# greento_schematic.net
KiCad netlist of a schematic drawn in Altium Designer
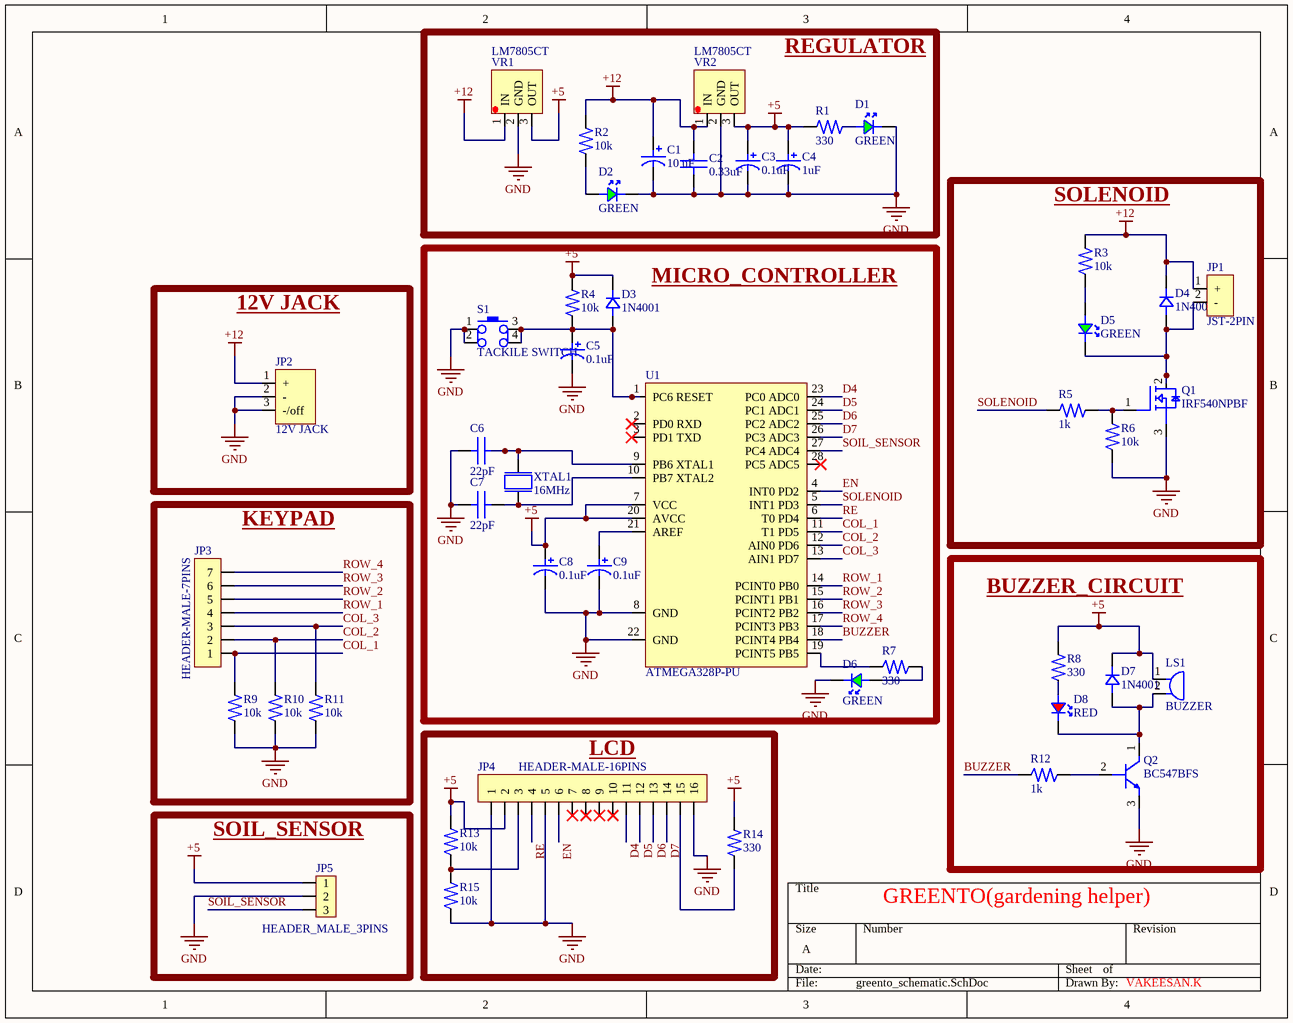
[diagram p0: greento_schematic.SchDoc]

(export (version "E")
  (design (tool "Eeschema 10.0.6"))
  (components
    (comp (ref "C1")
      (value "CAP ALUM 10UF 20% 450V RADIAL")
      (footprint "CAP ALUM 10UF 20% 450V RADIAL")
      (description "BXC Series 450 V 10 µF 10x20mm Aluminum Electrolytic Capacitor")
      (fields
        (field (name "MANUFACTURER") "Rubycon")
        (field (name "MANUFACTURER PART NUMBER") "450BXC10MEFC10X20")
        (field (name "SUPPLIER PART NUMBER 1") "10 uF")
      )
      (libsource (lib "schlib2") (part "450BXC10MEFC10X20"))
    )
    (comp (ref "C2")
      (value "CAP CER 0.33UF 50V X7R RADIAL")
      (footprint "CAP CER 0.33UF 50V X7R RADIAL")
      (description "Cap Ceramic 0.33uF 50V X7R 10% Radial 5mm 125C Bulk")
      (fields
        (field (name "MANUFACTURER") "TDK")
        (field (name "MANUFACTURER PART NUMBER") "FK24X7R1H334K")
        (field (name "SUPPLIER PART NUMBER 1") "0.33uF")
      )
      (libsource (lib "schlib2") (part "FK24X7R1H334K"))
    )
    (comp (ref "C3")
      (value "CAP ALUM 0.1UF 20% 50V RADIAL")
      (footprint "CAP ALUM 0.1UF 20% 50V RADIAL")
      (fields
        (field (name "MANUFACTURER") "Nichicon")
        (field (name "MANUFACTURER PART NUMBER") "UVZ1H0R1MDD1TD")
        (field (name "TOLERANCE") "20%")
        (field (name "SUPPLIER PART NUMBER 1") "0.1uF")
      )
      (libsource (lib "schlib2") (part "UVZ1H0R1MDD1TD"))
    )
    (comp (ref "C4")
      (value "CAP ALUM 1UF 20% 100V RADIAL")
      (footprint "CAP ALUM 1UF 20% 100V RADIAL")
      (description "Cap Aluminum 1uF 100V 20% (5 X 11mm) Radial 2.5mm 21mA 2000 hr 85°C Ammo Pack")
      (fields
        (field (name "MANUFACTURER") "Nichicon")
        (field (name "MANUFACTURER PART NUMBER") "UVR2A010MDD1TD")
        (field (name "SUPPLIER PART NUMBER 1") "1uF")
      )
      (libsource (lib "schlib2") (part "UVR2A010MDD1TD"))
    )
    (comp (ref "C5")
      (value "CAP ALUM 0.1UF 20% 50V RADIAL")
      (footprint "CAP ALUM 0.1UF 20% 50V RADIAL")
      (fields
        (field (name "MANUFACTURER") "Nichicon")
        (field (name "MANUFACTURER PART NUMBER") "UVZ1H0R1MDD1TD")
        (field (name "TOLERANCE") "20%")
        (field (name "SUPPLIER PART NUMBER 1") "0.1uF")
      )
      (libsource (lib "schlib2") (part "UVZ1H0R1MDD1TD"))
    )
    (comp (ref "C6")
      (value "CAP CER 22PF 200V NP0 RADIAL")
      (footprint "CAP CER 22PF 200V NP0 RADIAL")
      (description "Cap Ceramic 22pF 200V C0G 5% Radial 5.08mm 125°C Extreme Low ESR Bulk")
      (fields
        (field (name "MANUFACTURER") "KEMET")
        (field (name "MANUFACTURER PART NUMBER") "C317C220J2G5TA")
        (field (name "SUPPLIER PART NUMBER 1") "22pF")
      )
      (libsource (lib "schlib2") (part "C317C220J2G5TA"))
    )
    (comp (ref "C7")
      (value "CAP CER 22PF 200V NP0 RADIAL")
      (footprint "CAP CER 22PF 200V NP0 RADIAL")
      (description "Cap Ceramic 22pF 200V C0G 5% Radial 5.08mm 125°C Extreme Low ESR Bulk")
      (fields
        (field (name "MANUFACTURER") "KEMET")
        (field (name "MANUFACTURER PART NUMBER") "C317C220J2G5TA")
        (field (name "SUPPLIER PART NUMBER 1") "22pF")
      )
      (libsource (lib "schlib2") (part "C317C220J2G5TA"))
    )
    (comp (ref "C8")
      (value "CAP ALUM 0.1UF 20% 50V RADIAL")
      (footprint "CAP ALUM 0.1UF 20% 50V RADIAL")
      (fields
        (field (name "MANUFACTURER") "Nichicon")
        (field (name "MANUFACTURER PART NUMBER") "UVZ1H0R1MDD1TD")
        (field (name "TOLERANCE") "20%")
        (field (name "SUPPLIER PART NUMBER 1") "0.1uF")
      )
      (libsource (lib "schlib2") (part "UVZ1H0R1MDD1TD"))
    )
    (comp (ref "C9")
      (value "CAP ALUM 0.1UF 20% 50V RADIAL")
      (footprint "CAP ALUM 0.1UF 20% 50V RADIAL")
      (fields
        (field (name "MANUFACTURER") "Nichicon")
        (field (name "MANUFACTURER PART NUMBER") "UVZ1H0R1MDD1TD")
        (field (name "TOLERANCE") "20%")
        (field (name "SUPPLIER PART NUMBER 1") "0.1uF")
      )
      (libsource (lib "schlib2") (part "UVZ1H0R1MDD1TD"))
    )
    (comp (ref "D1")
      (value "LED GREEN CLEAR T-1 3/4 T/H")
      (footprint "LED GREEN CLEAR T-1 3/4 T/H")
      (description "Green 5 mm T-13/4 40° Diffused 29 mcd 2.1 V LED Through Hole")
      (fields
        (field (name "MANUFACTURER") "Vishay Lite-On")
        (field (name "MANUFACTURER PART NUMBER") "LTL-307GE")
        (field (name "SUPPLIER PART NUMBER 1") "GREEN")
      )
      (libsource (lib "schlib2") (part "LTL-307GE"))
    )
    (comp (ref "D2")
      (value "LED GREEN CLEAR T-1 3/4 T/H")
      (footprint "LED GREEN CLEAR T-1 3/4 T/H")
      (description "Green 5 mm T-13/4 40° Diffused 29 mcd 2.1 V LED Through Hole")
      (fields
        (field (name "MANUFACTURER") "Vishay Lite-On")
        (field (name "MANUFACTURER PART NUMBER") "LTL-307GE")
        (field (name "SUPPLIER PART NUMBER 1") "GREEN")
      )
      (libsource (lib "schlib2") (part "LTL-307GE"))
    )
    (comp (ref "D3")
      (value "DIODE GEN PURP 50V 1A DO41")
      (footprint "Diode 1N001")
      (description "Diode Switching 50V 1A 2-Pin DO-41 Bag")
      (fields
        (field (name "MANUFACTURER") "ON Semiconductor")
        (field (name "MANUFACTURER PART NUMBER") "1N4001G")
        (field (name "SUPPLIER PART NUMBER 1") "1N4001")
      )
      (libsource (lib "schlib2") (part "1N4001G"))
    )
    (comp (ref "D4")
      (value "DIODE GEN PURP 50V 1A DO41")
      (footprint "Diode 1N001")
      (description "Diode Switching 50V 1A 2-Pin DO-41 Bag")
      (fields
        (field (name "MANUFACTURER") "ON Semiconductor")
        (field (name "MANUFACTURER PART NUMBER") "1N4001G")
        (field (name "SUPPLIER PART NUMBER 1") "1N4001")
      )
      (libsource (lib "schlib2") (part "1N4001G"))
    )
    (comp (ref "D5")
      (value "LED GREEN CLEAR T-1 3/4 T/H")
      (footprint "LED GREEN CLEAR T-1 3/4 T/H")
      (description "Green 5 mm T-13/4 40° Diffused 29 mcd 2.1 V LED Through Hole")
      (fields
        (field (name "MANUFACTURER") "Vishay Lite-On")
        (field (name "MANUFACTURER PART NUMBER") "LTL-307GE")
        (field (name "SUPPLIER PART NUMBER 1") "GREEN")
      )
      (libsource (lib "schlib2") (part "LTL-307GE"))
    )
    (comp (ref "D6")
      (value "LED GREEN CLEAR T-1 3/4 T/H")
      (footprint "LED GREEN CLEAR T-1 3/4 T/H")
      (description "Green 5 mm T-13/4 40° Diffused 29 mcd 2.1 V LED Through Hole")
      (fields
        (field (name "MANUFACTURER") "Vishay Lite-On")
        (field (name "MANUFACTURER PART NUMBER") "LTL-307GE")
        (field (name "SUPPLIER PART NUMBER 1") "GREEN")
      )
      (libsource (lib "schlib2") (part "LTL-307GE"))
    )
    (comp (ref "D7")
      (value "DIODE GEN PURP 50V 1A DO41")
      (footprint "Diode 1N001")
      (description "Diode Switching 50V 1A 2-Pin DO-41 Bag")
      (fields
        (field (name "MANUFACTURER") "ON Semiconductor")
        (field (name "MANUFACTURER PART NUMBER") "1N4001G")
        (field (name "SUPPLIER PART NUMBER 1") "1N4001")
      )
      (libsource (lib "schlib2") (part "1N4001G"))
    )
    (comp (ref "D8")
      (value "LED RED DIFFUSED T-1 3/4 T/H")
      (footprint "RED GREEN CLEAR T-1 3/4 T/H")
      (description "Red 5 mm 50° Tinted Diffused 5.6 mcd 2.1 V LED Through Hole")
      (fields
        (field (name "MANUFACTURER") "Vishay Lite-On")
        (field (name "MANUFACTURER PART NUMBER") "LTL-307P")
        (field (name "SUPPLIER PART NUMBER 1") "RED")
      )
      (libsource (lib "schlib2") (part "LTL-307P"))
    )
    (comp (ref "JP1")
      (value "CONN HEADER VERT 2POS 2.5MM")
      (footprint "CONN HEADER VERT 2POS 2.5MM")
      (description "Conn Shrouded Header (4 Sides) HDR 2 POS 2.5mm Solder ST Thru-Hole Box")
      (fields
        (field (name "MANUFACTURER") "JST")
        (field (name "MANUFACTURER PART NUMBER") "B2B-XH-A(LF)(SN)")
        (field (name "SUPPLIER PART NUMBER 1") "JST-2PIN")
      )
      (libsource (lib "schlib2") (part "B2B-XH-A(LF)(SN)"))
    )
    (comp (ref "JP2")
      (value "PJ-002A")
      (footprint "CONN PWR JACK 2X5.5MM SOLDER")
      (description "2.0 x 6.5 mm, 2.5 A, Horizontal, Through Hole, Dc Power Jack Connector")
      (fields (field (name "MANUFACTURER") "CUI") (field (name "SUPPLIER PART NUMBER 1") "12V JACK"))
      (libsource (lib "schlib2") (part "PJ-002A"))
    )
    (comp (ref "JP3")
      (value "CONN HEADER VERT 07POS 2.54MM")
      (footprint "HEADER MALE 7 PIN")
      (description "07 Position Through-Hole Single Row Straight .100 Header")
      (fields
        (field (name "MANUFACTURER") "Sullins")
        (field (name "MANUFACTURER PART NUMBER") "PRPC040SACN-RC")
        (field (name "SUPPLIER PART NUMBER 1") "HEADER-MALE-7PINS")
      )
      (libsource (lib "schlib2") (part "PRPC007SACN-RC"))
    )
    (comp (ref "JP4")
      (value "CONN HEADER VERT 16POS 2.54MM")
      (footprint "header male 16 pin")
      (description "16 Position Through-Hole Single Row Straight .100 Header")
      (fields
        (field (name "MANUFACTURER") "Sullins")
        (field (name "MANUFACTURER PART NUMBER") "PRPC040SACN-RC")
        (field (name "SUPPLIER PART NUMBER 1") "HEADER-MALE-16PINS")
      )
      (libsource (lib "schlib2") (part "PRPC016SACN-RC"))
    )
    (comp (ref "JP5")
      (value "CONN HEADER VERT 03POS 2.54MM")
      (footprint "HEADER MALE 3 PIN")
      (description "03 Position Through-Hole Single Row Straight .100 Header")
      (fields
        (field (name "MANUFACTURER") "Sullins")
        (field (name "MANUFACTURER PART NUMBER") "PRPC040SACN-RC")
        (field (name "SUPPLIER PART NUMBER 1") "HEADER_MALE_3PINS")
      )
      (libsource (lib "schlib2") (part "PRPC040SACN-RC"))
    )
    (comp (ref "LS1")
      (value "BUZZER PIEZO 5V 13.9MM TH")
      (footprint "BUZZER PIEZO 5V 13.9MM TH")
      (description "13.9 mm, 5 Vdc, 83 dB, Through Hole, Driving Circuit, Piezo Audio Indicator Buzzer")
      (fields
        (field (name "MANUFACTURER") "CUI")
        (field (name "MANUFACTURER PART NUMBER") "CPI-137-83T")
        (field (name "SUPPLIER PART NUMBER 1") "BUZZER")
      )
      (libsource (lib "schlib2") (part "CPI-137-83T"))
    )
    (comp (ref "Q1")
      (value "MOSFET N-CH 100V 33A TO220AB")
      (footprint "IRF540NPBF")
      (description "Mosfet, Power; N-ch; Vdss 100V; Rds(on) 44MILLIOHMS; Id 33A; TO-220AB; Pd 130W; -55DEG")
      (fields
        (field (name "MANUFACTURER") "International Rectifier")
        (field (name "MANUFACTURER PART NUMBER") "IRF540NPBF")
        (field (name "SUPPLIER PART NUMBER 1") "IRF540NPBF")
      )
      (libsource (lib "schlib2") (part "IRF540NPBF"))
    )
    (comp (ref "Q2")
      (value "TRANS NPN 45V 0.1A TO92-3")
      (footprint "BC547B")
      (description "Trans GP BJT NPN 45V 0.1A 500mW Automotive 3-Pin TO-92 Ammo")
      (fields
        (field (name "MANUFACTURER") "ON Semiconductor / Fairchild")
        (field (name "MANUFACTURER PART NUMBER") "BC547B")
        (field (name "SUPPLIER PART NUMBER 1") "BC547BFS")
      )
      (libsource (lib "schlib2") (part "BC547B"))
    )
    (comp (ref "R1")
      (value "RES 330 OHM 5% 1/2W AXIAL")
      (footprint "RES 330 OHM 5% 1/2W AXIAL")
      (description "Res Carbon Film 330 Ohm 5% 1/2W -400ppm/°C to 0ppm/°C Conformal AXL Thru-Hole T/R")
      (fields
        (field (name "MANUFACTURER") "Stackpole Electronics")
        (field (name "MANUFACTURER PART NUMBER") "CFM12JT330R")
        (field (name "SUPPLIER PART NUMBER 1") "330")
      )
      (libsource (lib "schlib2") (part "CFM12JT330R"))
    )
    (comp (ref "R2")
      (value "RES 10K OHM 5% 1/4W AXIAL")
      (footprint "RES 10K OHM 5% 1/4W AXIAL")
      (description "Res Carbon Film 10K Ohm 5% 0.25W(1/4W) -500ppm/¦")
      (fields
        (field (name "MANUFACTURER") "Stackpole Electronics")
        (field (name "MANUFACTURER PART NUMBER") "CF14JT10K0")
        (field (name "SUPPLIER PART NUMBER 1") "10k")
      )
      (libsource (lib "schlib2") (part "CF14JT10K0"))
    )
    (comp (ref "R3")
      (value "RES 10K OHM 5% 1/4W AXIAL")
      (footprint "RES 10K OHM 5% 1/4W AXIAL")
      (description "Res Carbon Film 10K Ohm 5% 0.25W(1/4W) -500ppm/¦")
      (fields
        (field (name "MANUFACTURER") "Stackpole Electronics")
        (field (name "MANUFACTURER PART NUMBER") "CF14JT10K0")
        (field (name "SUPPLIER PART NUMBER 1") "10k")
      )
      (libsource (lib "schlib2") (part "CF14JT10K0"))
    )
    (comp (ref "R4")
      (value "RES 10K OHM 5% 1/4W AXIAL")
      (footprint "RES 10K OHM 5% 1/4W AXIAL")
      (description "Res Carbon Film 10K Ohm 5% 0.25W(1/4W) -500ppm/¦")
      (fields
        (field (name "MANUFACTURER") "Stackpole Electronics")
        (field (name "MANUFACTURER PART NUMBER") "CF14JT10K0")
        (field (name "SUPPLIER PART NUMBER 1") "10k")
      )
      (libsource (lib "schlib2") (part "CF14JT10K0"))
    )
    (comp (ref "R5")
      (value "RES 1K OHM 5% 1/4W AXIAL")
      (footprint "RES 1K OHM 5% 1/4W AXIAL")
      (description "Res Carbon Film 1K Ohm 5% 1/4W -400ppm/°C to 0ppm/°C Conformal AXL Thru-Hole T/R")
      (fields
        (field (name "MANUFACTURER") "Stackpole Electronics")
        (field (name "MANUFACTURER PART NUMBER") "CF14JT1K00")
        (field (name "SUPPLIER PART NUMBER 1") "1k")
      )
      (libsource (lib "schlib2") (part "CF14JT1K00"))
    )
    (comp (ref "R6")
      (value "RES 10K OHM 5% 1/4W AXIAL")
      (footprint "RES 10K OHM 5% 1/4W AXIAL")
      (description "Res Carbon Film 10K Ohm 5% 0.25W(1/4W) -500ppm/¦")
      (fields
        (field (name "MANUFACTURER") "Stackpole Electronics")
        (field (name "MANUFACTURER PART NUMBER") "CF14JT10K0")
        (field (name "SUPPLIER PART NUMBER 1") "10k")
      )
      (libsource (lib "schlib2") (part "CF14JT10K0"))
    )
    (comp (ref "R7")
      (value "RES 330 OHM 5% 1/2W AXIAL")
      (footprint "RES 330 OHM 5% 1/2W AXIAL")
      (description "Res Carbon Film 330 Ohm 5% 1/2W -400ppm/°C to 0ppm/°C Conformal AXL Thru-Hole T/R")
      (fields
        (field (name "MANUFACTURER") "Stackpole Electronics")
        (field (name "MANUFACTURER PART NUMBER") "CFM12JT330R")
        (field (name "SUPPLIER PART NUMBER 1") "330")
      )
      (libsource (lib "schlib2") (part "CFM12JT330R"))
    )
    (comp (ref "R8")
      (value "RES 330 OHM 5% 1/2W AXIAL")
      (footprint "RES 330 OHM 5% 1/2W AXIAL")
      (description "Res Carbon Film 330 Ohm 5% 1/2W -400ppm/°C to 0ppm/°C Conformal AXL Thru-Hole T/R")
      (fields
        (field (name "MANUFACTURER") "Stackpole Electronics")
        (field (name "MANUFACTURER PART NUMBER") "CFM12JT330R")
        (field (name "SUPPLIER PART NUMBER 1") "330")
      )
      (libsource (lib "schlib2") (part "CFM12JT330R"))
    )
    (comp (ref "R9")
      (value "RES 10K OHM 5% 1/4W AXIAL")
      (footprint "RES 10K OHM 5% 1/4W AXIAL")
      (description "Res Carbon Film 10K Ohm 5% 0.25W(1/4W) -500ppm/¦")
      (fields
        (field (name "MANUFACTURER") "Stackpole Electronics")
        (field (name "MANUFACTURER PART NUMBER") "CF14JT10K0")
        (field (name "SUPPLIER PART NUMBER 1") "10k")
      )
      (libsource (lib "schlib2") (part "CF14JT10K0"))
    )
    (comp (ref "R10")
      (value "RES 10K OHM 5% 1/4W AXIAL")
      (footprint "RES 10K OHM 5% 1/4W AXIAL")
      (description "Res Carbon Film 10K Ohm 5% 0.25W(1/4W) -500ppm/¦")
      (fields
        (field (name "MANUFACTURER") "Stackpole Electronics")
        (field (name "MANUFACTURER PART NUMBER") "CF14JT10K0")
        (field (name "SUPPLIER PART NUMBER 1") "10k")
      )
      (libsource (lib "schlib2") (part "CF14JT10K0"))
    )
    (comp (ref "R11")
      (value "RES 10K OHM 5% 1/4W AXIAL")
      (footprint "RES 10K OHM 5% 1/4W AXIAL")
      (description "Res Carbon Film 10K Ohm 5% 0.25W(1/4W) -500ppm/¦")
      (fields
        (field (name "MANUFACTURER") "Stackpole Electronics")
        (field (name "MANUFACTURER PART NUMBER") "CF14JT10K0")
        (field (name "SUPPLIER PART NUMBER 1") "10k")
      )
      (libsource (lib "schlib2") (part "CF14JT10K0"))
    )
    (comp (ref "R12")
      (value "RES 1K OHM 5% 1/4W AXIAL")
      (footprint "RES 1K OHM 5% 1/4W AXIAL")
      (description "Res Carbon Film 1K Ohm 5% 1/4W -400ppm/°C to 0ppm/°C Conformal AXL Thru-Hole T/R")
      (fields
        (field (name "MANUFACTURER") "Stackpole Electronics")
        (field (name "MANUFACTURER PART NUMBER") "CF14JT1K00")
        (field (name "SUPPLIER PART NUMBER 1") "1k")
      )
      (libsource (lib "schlib2") (part "CF14JT1K00"))
    )
    (comp (ref "R13")
      (value "RES 10K OHM 5% 1/4W AXIAL")
      (footprint "RES 10K OHM 5% 1/4W AXIAL")
      (description "Res Carbon Film 10K Ohm 5% 0.25W(1/4W) -500ppm/¦")
      (fields
        (field (name "MANUFACTURER") "Stackpole Electronics")
        (field (name "MANUFACTURER PART NUMBER") "CF14JT10K0")
        (field (name "SUPPLIER PART NUMBER 1") "10k")
      )
      (libsource (lib "schlib2") (part "CF14JT10K0"))
    )
    (comp (ref "R14")
      (value "RES 330 OHM 5% 1/2W AXIAL")
      (footprint "RES 330 OHM 5% 1/2W AXIAL")
      (description "Res Carbon Film 330 Ohm 5% 1/2W -400ppm/°C to 0ppm/°C Conformal AXL Thru-Hole T/R")
      (fields
        (field (name "MANUFACTURER") "Stackpole Electronics")
        (field (name "MANUFACTURER PART NUMBER") "CFM12JT330R")
        (field (name "SUPPLIER PART NUMBER 1") "330")
      )
      (libsource (lib "schlib2") (part "CFM12JT330R"))
    )
    (comp (ref "R15")
      (value "RES 10K OHM 5% 1/4W AXIAL")
      (footprint "RES 10K OHM 5% 1/4W AXIAL")
      (description "Res Carbon Film 10K Ohm 5% 0.25W(1/4W) -500ppm/¦")
      (fields
        (field (name "MANUFACTURER") "Stackpole Electronics")
        (field (name "MANUFACTURER PART NUMBER") "CF14JT10K0")
        (field (name "SUPPLIER PART NUMBER 1") "10k")
      )
      (libsource (lib "schlib2") (part "CF14JT10K0"))
    )
    (comp (ref "S1")
      (value "SWITCH TACTILE SPST-NO 0.05A 12V")
      (footprint "Tacktile switch")
      (description "Switch Tactile N.O. SPST Round Button PC Pins 0.05A 50VDC 1.57N Thru-Hole")
      (fields
        (field (name "MANUFACTURER") "E-Switch")
        (field (name "MANUFACTURER PART NUMBER") "TL1105BF160Q")
        (field (name "SUPPLIER PART NUMBER 1") "TACKILE SWITCH")
      )
      (libsource (lib "schlib2") (part "TL1105BF160Q"))
    )
    (comp (ref "U1")
      (value "AVR series Microcontroller IC 8-Bit 20MHz 32KB (16K x 16) FLASH 28-PDIP")
      (footprint "ATMEGA328P")
      (description "ATMEGA328P-PU")
      (fields
        (field (name "MANUFACTURER") "Microchip / Atmel")
        (field (name "SUPPLIER PART NUMBER 1") "ATMEGA328P-PU")
      )
      (libsource (lib "schlib2") (part "ATMEGA328P-PU"))
    )
    (comp (ref "VR1")
      (value "LM7805CT")
      (footprint "lm7805")
      (description "LM78XX Series 5 V Fixed Output 1 A 3-Terminal LDO Voltage Regulator - TO-220")
      (fields
        (field (name "MANUFACTURER") "ON Semiconductor / Fairchild")
        (field (name "SUPPLIER PART NUMBER 1") "LM7805CT")
      )
      (libsource (lib "schlib2") (part "LM7805CT"))
    )
    (comp (ref "VR2")
      (value "LM7805CT")
      (footprint "lm7805")
      (description "LM78XX Series 5 V Fixed Output 1 A 3-Terminal LDO Voltage Regulator - TO-220")
      (fields
        (field (name "MANUFACTURER") "ON Semiconductor / Fairchild")
        (field (name "SUPPLIER PART NUMBER 1") "LM7805CT")
      )
      (libsource (lib "schlib2") (part "LM7805CT"))
    )
    (comp (ref "XTAL1")
      (value "CRYSTAL 16.0000MHZ 20PF TH")
      (footprint "CRYSTAL 16.0000MHZ 20PF TH")
      (description "Crystal 16MHz ±30ppm (Tol) ±50ppm (Stability) 20pF FUND 40Ohm 2-Pin HC-49/US Thru-Hole Bulk")
      (fields
        (field (name "MANUFACTURER") "CTS")
        (field (name "MANUFACTURER PART NUMBER") "ATS16A-E")
        (field (name "SUPPLIER PART NUMBER 1") "16MHz")
      )
      (libsource (lib "schlib2") (part "ATS16A-E"))
    )
  )
  (nets
    (net (code "1") (name "+5") (class "Default")
      (node (ref "C3") (pin "1") (pinfunction "+_1") (pintype "passive"))
      (node (ref "C4") (pin "1") (pinfunction "+_1") (pintype "passive"))
      (node (ref "C8") (pin "1") (pinfunction "+_1") (pintype "passive"))
      (node (ref "D3") (pin "K") (pinfunction "-_K") (pintype "passive"))
      (node (ref "D7") (pin "K") (pinfunction "-_K") (pintype "passive"))
      (node (ref "JP4") (pin "2") (pinfunction "2_2") (pintype "passive"))
      (node (ref "JP5") (pin "VCC") (pinfunction "1_VCC") (pintype "passive"))
      (node (ref "LS1") (pin "1") (pinfunction "+_1") (pintype "passive"))
      (node (ref "R1") (pin "1") (pinfunction "1_1") (pintype "passive"))
      (node (ref "R13") (pin "2") (pinfunction "2_2") (pintype "passive"))
      (node (ref "R14") (pin "2") (pinfunction "2_2") (pintype "passive"))
      (node (ref "R4") (pin "2") (pinfunction "2_2") (pintype "passive"))
      (node (ref "R8") (pin "1") (pinfunction "1_1") (pintype "passive"))
      (node (ref "U1") (pin "20") (pinfunction "AVCC_20") (pintype "passive"))
      (node (ref "U1") (pin "7") (pinfunction "VCC_7") (pintype "passive"))
      (node (ref "VR1") (pin "3") (pinfunction "OUT_3") (pintype "power_in"))
      (node (ref "VR2") (pin "3") (pinfunction "OUT_3") (pintype "power_in"))
    )
    (net (code "2") (name "+12") (class "Default")
      (node (ref "C1") (pin "1") (pinfunction "+_1") (pintype "passive"))
      (node (ref "C2") (pin "2") (pinfunction "2_2") (pintype "passive"))
      (node (ref "D4") (pin "K") (pinfunction "-_K") (pintype "passive"))
      (node (ref "JP1") (pin "1") (pinfunction "+_1") (pintype "passive"))
      (node (ref "JP2") (pin "1") (pinfunction "+_1") (pintype "passive"))
      (node (ref "R2") (pin "2") (pinfunction "2_2") (pintype "passive"))
      (node (ref "R3") (pin "1") (pinfunction "1_1") (pintype "passive"))
      (node (ref "VR1") (pin "1") (pinfunction "IN_1") (pintype "power_in"))
      (node (ref "VR2") (pin "1") (pinfunction "IN_1") (pintype "power_in"))
    )
    (net (code "3") (name "/BUZZER") (class "Default")
      (node (ref "R12") (pin "1") (pinfunction "1_1") (pintype "passive"))
      (node (ref "U1") (pin "18") (pinfunction "PCINT4_PB4_18") (pintype "passive"))
    )
    (net (code "4") (name "/COL_1") (class "Default")
      (node (ref "JP3") (pin "1") (pinfunction "1_1") (pintype "passive"))
      (node (ref "R9") (pin "2") (pinfunction "2_2") (pintype "passive"))
      (node (ref "U1") (pin "11") (pinfunction "T1_PD5_11") (pintype "passive"))
    )
    (net (code "5") (name "/COL_2") (class "Default")
      (node (ref "JP3") (pin "2") (pinfunction "2_2") (pintype "passive"))
      (node (ref "R10") (pin "2") (pinfunction "2_2") (pintype "passive"))
      (node (ref "U1") (pin "12") (pinfunction "AIN0_PD6_12") (pintype "passive"))
    )
    (net (code "6") (name "/COL_3") (class "Default")
      (node (ref "JP3") (pin "3") (pinfunction "3_3") (pintype "passive"))
      (node (ref "R11") (pin "2") (pinfunction "2_2") (pintype "passive"))
      (node (ref "U1") (pin "13") (pinfunction "AIN1_PD7_13") (pintype "passive"))
    )
    (net (code "7") (name "/D4") (class "Default")
      (node (ref "JP4") (pin "11") (pinfunction "11_11") (pintype "passive"))
      (node (ref "U1") (pin "23") (pinfunction "PC0_ADC0_23") (pintype "passive"))
    )
    (net (code "8") (name "/D5") (class "Default")
      (node (ref "JP4") (pin "12") (pinfunction "12_12") (pintype "passive"))
      (node (ref "U1") (pin "24") (pinfunction "PC1_ADC1_24") (pintype "passive"))
    )
    (net (code "9") (name "/D6") (class "Default")
      (node (ref "JP4") (pin "13") (pinfunction "13_13") (pintype "passive"))
      (node (ref "U1") (pin "25") (pinfunction "PC2_ADC2_25") (pintype "passive"))
    )
    (net (code "10") (name "/D7") (class "Default")
      (node (ref "JP4") (pin "14") (pinfunction "14_14") (pintype "passive"))
      (node (ref "U1") (pin "26") (pinfunction "PC3_ADC3_26") (pintype "passive"))
    )
    (net (code "11") (name "/EN") (class "Default")
      (node (ref "JP4") (pin "6") (pinfunction "6_6") (pintype "passive"))
      (node (ref "U1") (pin "4") (pinfunction "INT0_PD2_4") (pintype "passive"))
    )
    (net (code "12") (name "/RE") (class "Default")
      (node (ref "JP4") (pin "4") (pinfunction "4_4") (pintype "passive"))
      (node (ref "U1") (pin "6") (pinfunction "T0_PD4_6") (pintype "passive"))
    )
    (net (code "13") (name "/ROW_1") (class "Default")
      (node (ref "JP3") (pin "4") (pinfunction "4_4") (pintype "passive"))
      (node (ref "U1") (pin "14") (pinfunction "PCINT0_PB0_14") (pintype "passive"))
    )
    (net (code "14") (name "/ROW_2") (class "Default")
      (node (ref "JP3") (pin "5") (pinfunction "5_5") (pintype "passive"))
      (node (ref "U1") (pin "15") (pinfunction "PCINT1_PB1_15") (pintype "passive"))
    )
    (net (code "15") (name "/ROW_3") (class "Default")
      (node (ref "JP3") (pin "6") (pinfunction "6_6") (pintype "passive"))
      (node (ref "U1") (pin "16") (pinfunction "PCINT2_PB2_16") (pintype "passive"))
    )
    (net (code "16") (name "/ROW_4") (class "Default")
      (node (ref "JP3") (pin "7") (pinfunction "7_7") (pintype "passive"))
      (node (ref "U1") (pin "17") (pinfunction "PCINT3_PB3_17") (pintype "passive"))
    )
    (net (code "17") (name "/SOIL_SENSOR") (class "Default")
      (node (ref "JP5") (pin "AIN") (pinfunction "3_AIN") (pintype "passive"))
      (node (ref "U1") (pin "27") (pinfunction "PC4_ADC4_27") (pintype "passive"))
    )
    (net (code "18") (name "/SOLENOID") (class "Default")
      (node (ref "R5") (pin "1") (pinfunction "1_1") (pintype "passive"))
      (node (ref "U1") (pin "5") (pinfunction "INT1_PD3_5") (pintype "passive"))
    )
    (net (code "19") (name "GND") (class "Default")
      (node (ref "C1") (pin "2") (pinfunction "-_2") (pintype "passive"))
      (node (ref "C2") (pin "1") (pinfunction "1_1") (pintype "passive"))
      (node (ref "C3") (pin "2") (pinfunction "-_2") (pintype "passive"))
      (node (ref "C4") (pin "2") (pinfunction "-_2") (pintype "passive"))
      (node (ref "C5") (pin "2") (pinfunction "-_2") (pintype "passive"))
      (node (ref "C6") (pin "2") (pinfunction "2_2") (pintype "passive"))
      (node (ref "C7") (pin "2") (pinfunction "2_2") (pintype "passive"))
      (node (ref "C8") (pin "2") (pinfunction "-_2") (pintype "passive"))
      (node (ref "C9") (pin "2") (pinfunction "-_2") (pintype "passive"))
      (node (ref "D1") (pin "K") (pinfunction "-_K") (pintype "passive"))
      (node (ref "D2") (pin "K") (pinfunction "-_K") (pintype "passive"))
      (node (ref "D6") (pin "K") (pinfunction "-_K") (pintype "passive"))
      (node (ref "JP2") (pin "2") (pinfunction "-_2") (pintype "passive"))
      (node (ref "JP2") (pin "3") (pinfunction "-/off_3") (pintype "passive"))
      (node (ref "JP4") (pin "1") (pinfunction "1_1") (pintype "passive"))
      (node (ref "JP4") (pin "16") (pinfunction "16_16") (pintype "passive"))
      (node (ref "JP4") (pin "5") (pinfunction "5_5") (pintype "passive"))
      (node (ref "JP5") (pin "GND") (pinfunction "2_GND") (pintype "passive"))
      (node (ref "Q1") (pin "3") (pinfunction "S_3") (pintype "passive"))
      (node (ref "Q2") (pin "3") (pinfunction "EMITTER_3") (pintype "passive"))
      (node (ref "R10") (pin "1") (pinfunction "1_1") (pintype "passive"))
      (node (ref "R11") (pin "1") (pinfunction "1_1") (pintype "passive"))
      (node (ref "R15") (pin "1") (pinfunction "1_1") (pintype "passive"))
      (node (ref "R6") (pin "1") (pinfunction "1_1") (pintype "passive"))
      (node (ref "R9") (pin "1") (pinfunction "1_1") (pintype "passive"))
      (node (ref "S1") (pin "1") (pinfunction "1_1") (pintype "passive"))
      (node (ref "S1") (pin "2") (pinfunction "2_2") (pintype "passive"))
      (node (ref "U1") (pin "22") (pinfunction "GND_22") (pintype "passive"))
      (node (ref "U1") (pin "8") (pinfunction "GND_8") (pintype "passive"))
      (node (ref "VR1") (pin "2") (pinfunction "GND_2") (pintype "power_in"))
      (node (ref "VR2") (pin "2") (pinfunction "GND_2") (pintype "power_in"))
    )
    (net (code "20") (name "Net-(C5-+)") (class "Default")
      (node (ref "C5") (pin "1") (pinfunction "+_1") (pintype "passive"))
      (node (ref "D3") (pin "A") (pinfunction "+_A") (pintype "passive"))
      (node (ref "R4") (pin "1") (pinfunction "1_1") (pintype "passive"))
      (node (ref "S1") (pin "3") (pinfunction "3_3") (pintype "passive"))
      (node (ref "S1") (pin "4") (pinfunction "4_4") (pintype "passive"))
      (node (ref "U1") (pin "1") (pinfunction "PC6_RESET_1") (pintype "passive"))
    )
    (net (code "21") (name "Net-(C9-+)") (class "Default")
      (node (ref "C9") (pin "1") (pinfunction "+_1") (pintype "passive"))
      (node (ref "U1") (pin "21") (pinfunction "AREF_21") (pintype "passive"))
    )
    (net (code "22") (name "Net-(D1-+)") (class "Default")
      (node (ref "D1") (pin "A") (pinfunction "+_A") (pintype "passive"))
      (node (ref "R1") (pin "2") (pinfunction "2_2") (pintype "passive"))
    )
    (net (code "23") (name "Net-(D2-+)") (class "Default")
      (node (ref "D2") (pin "A") (pinfunction "+_A") (pintype "passive"))
      (node (ref "R2") (pin "1") (pinfunction "1_1") (pintype "passive"))
    )
    (net (code "24") (name "Net-(D4-+)") (class "Default")
      (node (ref "D4") (pin "A") (pinfunction "+_A") (pintype "passive"))
      (node (ref "D5") (pin "K") (pinfunction "-_K") (pintype "passive"))
      (node (ref "JP1") (pin "2") (pinfunction "-_2") (pintype "passive"))
      (node (ref "Q1") (pin "2") (pinfunction "D_2") (pintype "passive"))
    )
    (net (code "25") (name "Net-(D5-+)") (class "Default")
      (node (ref "D5") (pin "A") (pinfunction "+_A") (pintype "passive"))
      (node (ref "R3") (pin "2") (pinfunction "2_2") (pintype "passive"))
    )
    (net (code "26") (name "Net-(D6-+)") (class "Default")
      (node (ref "D6") (pin "A") (pinfunction "+_A") (pintype "passive"))
      (node (ref "R7") (pin "2") (pinfunction "2_2") (pintype "passive"))
    )
    (net (code "27") (name "Net-(D7-+)") (class "Default")
      (node (ref "D7") (pin "A") (pinfunction "+_A") (pintype "passive"))
      (node (ref "D8") (pin "K") (pinfunction "-_K") (pintype "passive"))
      (node (ref "LS1") (pin "2") (pinfunction "-_2") (pintype "passive"))
      (node (ref "Q2") (pin "1") (pinfunction "COLLECTOR_1") (pintype "passive"))
    )
    (net (code "28") (name "Net-(D8-+)") (class "Default")
      (node (ref "D8") (pin "A") (pinfunction "+_A") (pintype "passive"))
      (node (ref "R8") (pin "2") (pinfunction "2_2") (pintype "passive"))
    )
    (net (code "29") (name "Net-(JP4-Pad3)") (class "Default")
      (node (ref "JP4") (pin "3") (pinfunction "3_3") (pintype "passive"))
      (node (ref "R13") (pin "1") (pinfunction "1_1") (pintype "passive"))
      (node (ref "R15") (pin "2") (pinfunction "2_2") (pintype "passive"))
    )
    (net (code "30") (name "Net-(JP4-Pad15)") (class "Default")
      (node (ref "JP4") (pin "15") (pinfunction "15_15") (pintype "passive"))
      (node (ref "R14") (pin "1") (pinfunction "1_1") (pintype "passive"))
    )
    (net (code "31") (name "Net-(Q1-G)") (class "Default")
      (node (ref "Q1") (pin "1") (pinfunction "G_1") (pintype "passive"))
      (node (ref "R5") (pin "2") (pinfunction "2_2") (pintype "passive"))
      (node (ref "R6") (pin "2") (pinfunction "2_2") (pintype "passive"))
    )
    (net (code "32") (name "Net-(Q2-BASE)") (class "Default")
      (node (ref "Q2") (pin "2") (pinfunction "BASE_2") (pintype "passive"))
      (node (ref "R12") (pin "2") (pinfunction "2_2") (pintype "passive"))
    )
    (net (code "33") (name "Net-(U1-PB6_XTAL1)") (class "Default")
      (node (ref "C6") (pin "1") (pinfunction "1_1") (pintype "passive"))
      (node (ref "U1") (pin "9") (pinfunction "PB6_XTAL1_9") (pintype "passive"))
      (node (ref "XTAL1") (pin "2") (pinfunction "PIN2_2") (pintype "passive"))
    )
    (net (code "34") (name "Net-(U1-PB7_XTAL2)") (class "Default")
      (node (ref "C7") (pin "1") (pinfunction "1_1") (pintype "passive"))
      (node (ref "U1") (pin "10") (pinfunction "PB7_XTAL2_10") (pintype "passive"))
      (node (ref "XTAL1") (pin "1") (pinfunction "PIN1_1") (pintype "passive"))
    )
    (net (code "35") (name "Net-(U1-PCINT5_PB5)") (class "Default")
      (node (ref "R7") (pin "1") (pinfunction "1_1") (pintype "passive"))
      (node (ref "U1") (pin "19") (pinfunction "PCINT5_PB5_19") (pintype "passive"))
    )
    (net (code "36") (name "unconnected-(JP4-Pad7)") (class "Default")
      (node (ref "JP4") (pin "7") (pinfunction "7_7") (pintype "passive+no_connect"))
    )
    (net (code "37") (name "unconnected-(JP4-Pad8)") (class "Default")
      (node (ref "JP4") (pin "8") (pinfunction "8_8") (pintype "passive+no_connect"))
    )
    (net (code "38") (name "unconnected-(JP4-Pad9)") (class "Default")
      (node (ref "JP4") (pin "9") (pinfunction "9_9") (pintype "passive+no_connect"))
    )
    (net (code "39") (name "unconnected-(JP4-Pad10)") (class "Default")
      (node (ref "JP4") (pin "10") (pinfunction "10_10") (pintype "passive+no_connect"))
    )
    (net (code "40") (name "unconnected-(U1-PC5_ADC5-Pad28)") (class "Default")
      (node (ref "U1") (pin "28") (pinfunction "PC5_ADC5_28") (pintype "passive+no_connect"))
    )
    (net (code "41") (name "unconnected-(U1-PD0_RXD-Pad2)") (class "Default")
      (node (ref "U1") (pin "2") (pinfunction "PD0_RXD_2") (pintype "passive+no_connect"))
    )
    (net (code "42") (name "unconnected-(U1-PD1_TXD-Pad3)") (class "Default")
      (node (ref "U1") (pin "3") (pinfunction "PD1_TXD_3") (pintype "passive+no_connect"))
    )
  )
)
